# 16_FPGA_pwr_banks.net
KiCad netlist of a schematic drawn in Altium Designer
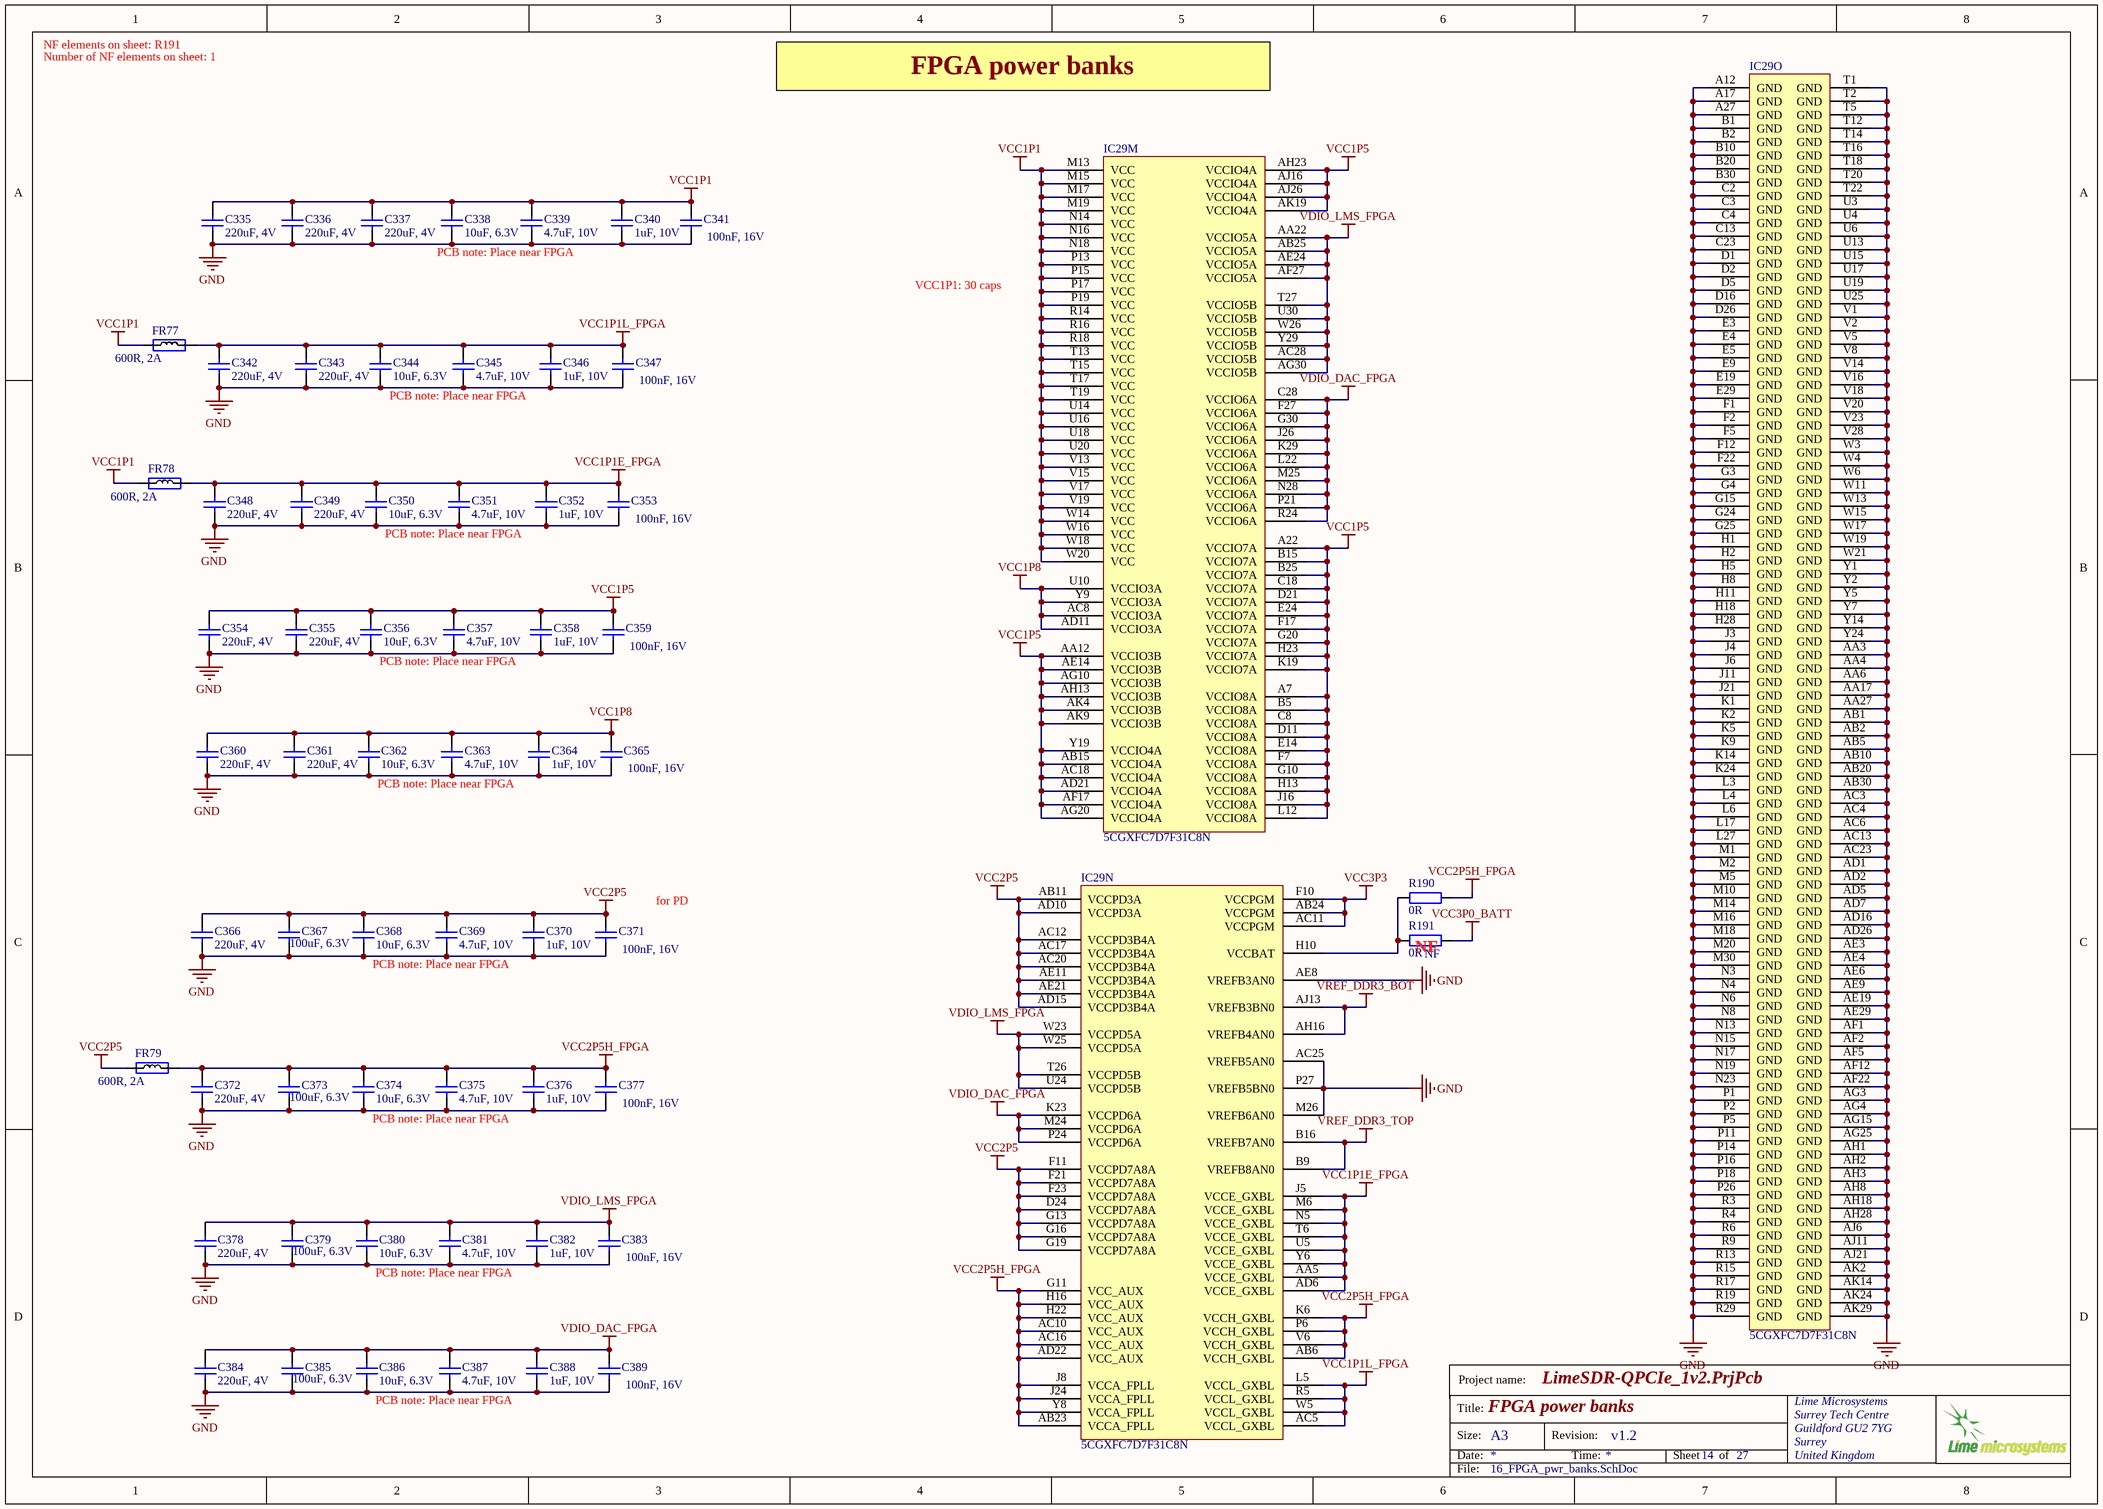
[diagram p0: 16_FPGA_pwr_banks.SchDoc]

(export (version "E")
  (design (tool "Eeschema 10.0.6"))
  (components
    (comp (ref "C335")
      (value "220uF, 4V")
      (footprint "CAP1206")
      (fields
        (field (name "MANUFACTURER PART NUMBER") "GRM31CR60G227ME11L")
        (field (name "MANUFACTURER") "Murata Electronics North America")
        (field (name "TOLERANCE") "±20%")
      )
      (libsource (lib "LimeFPGAboard_schLib") (part "Cap_1206"))
    )
    (comp (ref "C336")
      (value "220uF, 4V")
      (footprint "CAP1206")
      (fields
        (field (name "MANUFACTURER PART NUMBER") "GRM31CR60G227ME11L")
        (field (name "MANUFACTURER") "Murata Electronics North America")
        (field (name "TOLERANCE") "±20%")
      )
      (libsource (lib "LimeFPGAboard_schLib") (part "Cap_1206"))
    )
    (comp (ref "C337")
      (value "220uF, 4V")
      (footprint "CAP1206")
      (fields
        (field (name "MANUFACTURER PART NUMBER") "GRM31CR60G227ME11L")
        (field (name "MANUFACTURER") "Murata Electronics North America")
        (field (name "TOLERANCE") "±20%")
      )
      (libsource (lib "LimeFPGAboard_schLib") (part "Cap_1206"))
    )
    (comp (ref "C338")
      (value "10uF, 6.3V")
      (footprint "CAP0603")
      (fields (field (name "TOLERANCE") "±20%") (field (name "MANUFACTURER") "Yageo"))
      (libsource (lib "LimeFPGAboard_schLib") (part "Cap_0603"))
    )
    (comp (ref "C339")
      (value "4.7uF, 10V")
      (footprint "CAP0603")
      (fields (field (name "TOLERANCE") "10 %") (field (name "MANUFACTURER") "TDK Corporation"))
      (libsource (lib "LimeFPGAboard_schLib") (part "Cap_0603"))
    )
    (comp (ref "C340")
      (value "1uF, 10V")
      (footprint "CAP0402")
      (fields (field (name "MANUFACTURER") "TDK"))
      (libsource (lib "LimeMicroAltiumLib_schLib") (part "Cap_0402"))
    )
    (comp (ref "C341")
      (value "100nF, 16V")
      (footprint "CAP0402")
      (fields
        (field (name "TOLERANCE") "10 %")
        (field (name "MANUFACTURER") "Murata Electronics")
        (field (name "MANUFACTURER PART NUMBER") "GRM155R71C104KA88D")
      )
      (libsource (lib "LimeFPGAboard_schLib") (part "Cap_0603"))
    )
    (comp (ref "C342")
      (value "220uF, 4V")
      (footprint "CAP1206")
      (fields
        (field (name "MANUFACTURER PART NUMBER") "GRM31CR60G227ME11L")
        (field (name "MANUFACTURER") "Murata Electronics North America")
        (field (name "TOLERANCE") "±20%")
      )
      (libsource (lib "LimeFPGAboard_schLib") (part "Cap_1206"))
    )
    (comp (ref "C343")
      (value "220uF, 4V")
      (footprint "CAP1206")
      (fields
        (field (name "MANUFACTURER PART NUMBER") "GRM31CR60G227ME11L")
        (field (name "MANUFACTURER") "Murata Electronics North America")
        (field (name "TOLERANCE") "±20%")
      )
      (libsource (lib "LimeFPGAboard_schLib") (part "Cap_1206"))
    )
    (comp (ref "C344")
      (value "10uF, 6.3V")
      (footprint "CAP0603")
      (fields (field (name "TOLERANCE") "±20%") (field (name "MANUFACTURER") "Yageo"))
      (libsource (lib "LimeFPGAboard_schLib") (part "Cap_0603"))
    )
    (comp (ref "C345")
      (value "4.7uF, 10V")
      (footprint "CAP0603")
      (fields (field (name "TOLERANCE") "10 %") (field (name "MANUFACTURER") "TDK Corporation"))
      (libsource (lib "LimeFPGAboard_schLib") (part "Cap_0603"))
    )
    (comp (ref "C346")
      (value "1uF, 10V")
      (footprint "CAP0402")
      (fields (field (name "MANUFACTURER") "TDK"))
      (libsource (lib "LimeMicroAltiumLib_schLib") (part "Cap_0402"))
    )
    (comp (ref "C347")
      (value "100nF, 16V")
      (footprint "CAP0402")
      (fields
        (field (name "TOLERANCE") "10 %")
        (field (name "MANUFACTURER") "Murata Electronics")
        (field (name "MANUFACTURER PART NUMBER") "GRM155R71C104KA88D")
      )
      (libsource (lib "LimeFPGAboard_schLib") (part "Cap_0603"))
    )
    (comp (ref "C348")
      (value "220uF, 4V")
      (footprint "CAP1206")
      (fields
        (field (name "MANUFACTURER PART NUMBER") "GRM31CR60G227ME11L")
        (field (name "MANUFACTURER") "Murata Electronics North America")
        (field (name "TOLERANCE") "±20%")
      )
      (libsource (lib "LimeFPGAboard_schLib") (part "Cap_1206"))
    )
    (comp (ref "C349")
      (value "220uF, 4V")
      (footprint "CAP1206")
      (fields
        (field (name "MANUFACTURER PART NUMBER") "GRM31CR60G227ME11L")
        (field (name "MANUFACTURER") "Murata Electronics North America")
        (field (name "TOLERANCE") "±20%")
      )
      (libsource (lib "LimeFPGAboard_schLib") (part "Cap_1206"))
    )
    (comp (ref "C350")
      (value "10uF, 6.3V")
      (footprint "CAP0603")
      (fields (field (name "TOLERANCE") "±20%") (field (name "MANUFACTURER") "Yageo"))
      (libsource (lib "LimeFPGAboard_schLib") (part "Cap_0603"))
    )
    (comp (ref "C351")
      (value "4.7uF, 10V")
      (footprint "CAP0603")
      (fields (field (name "TOLERANCE") "10 %") (field (name "MANUFACTURER") "TDK Corporation"))
      (libsource (lib "LimeFPGAboard_schLib") (part "Cap_0603"))
    )
    (comp (ref "C352")
      (value "1uF, 10V")
      (footprint "CAP0402")
      (fields (field (name "MANUFACTURER") "TDK"))
      (libsource (lib "LimeMicroAltiumLib_schLib") (part "Cap_0402"))
    )
    (comp (ref "C353")
      (value "100nF, 16V")
      (footprint "CAP0402")
      (fields
        (field (name "TOLERANCE") "10 %")
        (field (name "MANUFACTURER") "Murata Electronics")
        (field (name "MANUFACTURER PART NUMBER") "GRM155R71C104KA88D")
      )
      (libsource (lib "LimeFPGAboard_schLib") (part "Cap_0603"))
    )
    (comp (ref "C354")
      (value "220uF, 4V")
      (footprint "CAP1206")
      (fields
        (field (name "MANUFACTURER PART NUMBER") "GRM31CR60G227ME11L")
        (field (name "MANUFACTURER") "Murata Electronics North America")
        (field (name "TOLERANCE") "±20%")
      )
      (libsource (lib "LimeFPGAboard_schLib") (part "Cap_1206"))
    )
    (comp (ref "C355")
      (value "220uF, 4V")
      (footprint "CAP1206")
      (fields
        (field (name "MANUFACTURER PART NUMBER") "GRM31CR60G227ME11L")
        (field (name "MANUFACTURER") "Murata Electronics North America")
        (field (name "TOLERANCE") "±20%")
      )
      (libsource (lib "LimeFPGAboard_schLib") (part "Cap_1206"))
    )
    (comp (ref "C356")
      (value "10uF, 6.3V")
      (footprint "CAP0603")
      (fields (field (name "TOLERANCE") "±20%") (field (name "MANUFACTURER") "Yageo"))
      (libsource (lib "LimeFPGAboard_schLib") (part "Cap_0603"))
    )
    (comp (ref "C357")
      (value "4.7uF, 10V")
      (footprint "CAP0603")
      (fields (field (name "TOLERANCE") "10 %") (field (name "MANUFACTURER") "TDK Corporation"))
      (libsource (lib "LimeFPGAboard_schLib") (part "Cap_0603"))
    )
    (comp (ref "C358")
      (value "1uF, 10V")
      (footprint "CAP0402")
      (fields (field (name "MANUFACTURER") "TDK"))
      (libsource (lib "LimeMicroAltiumLib_schLib") (part "Cap_0402"))
    )
    (comp (ref "C359")
      (value "100nF, 16V")
      (footprint "CAP0402")
      (fields
        (field (name "TOLERANCE") "10 %")
        (field (name "MANUFACTURER") "Murata Electronics")
        (field (name "MANUFACTURER PART NUMBER") "GRM155R71C104KA88D")
      )
      (libsource (lib "LimeFPGAboard_schLib") (part "Cap_0603"))
    )
    (comp (ref "C360")
      (value "220uF, 4V")
      (footprint "CAP1206")
      (fields
        (field (name "MANUFACTURER PART NUMBER") "GRM31CR60G227ME11L")
        (field (name "MANUFACTURER") "Murata Electronics North America")
        (field (name "TOLERANCE") "±20%")
      )
      (libsource (lib "LimeFPGAboard_schLib") (part "Cap_1206"))
    )
    (comp (ref "C361")
      (value "220uF, 4V")
      (footprint "CAP1206")
      (fields
        (field (name "MANUFACTURER PART NUMBER") "GRM31CR60G227ME11L")
        (field (name "MANUFACTURER") "Murata Electronics North America")
        (field (name "TOLERANCE") "±20%")
      )
      (libsource (lib "LimeFPGAboard_schLib") (part "Cap_1206"))
    )
    (comp (ref "C362")
      (value "10uF, 6.3V")
      (footprint "CAP0603")
      (fields (field (name "TOLERANCE") "±20%") (field (name "MANUFACTURER") "Yageo"))
      (libsource (lib "LimeFPGAboard_schLib") (part "Cap_0603"))
    )
    (comp (ref "C363")
      (value "4.7uF, 10V")
      (footprint "CAP0603")
      (fields (field (name "TOLERANCE") "10 %") (field (name "MANUFACTURER") "TDK Corporation"))
      (libsource (lib "LimeFPGAboard_schLib") (part "Cap_0603"))
    )
    (comp (ref "C364")
      (value "1uF, 10V")
      (footprint "CAP0402")
      (fields (field (name "MANUFACTURER") "TDK"))
      (libsource (lib "LimeMicroAltiumLib_schLib") (part "Cap_0402"))
    )
    (comp (ref "C365")
      (value "100nF, 16V")
      (footprint "CAP0402")
      (fields
        (field (name "TOLERANCE") "10 %")
        (field (name "MANUFACTURER") "Murata Electronics")
        (field (name "MANUFACTURER PART NUMBER") "GRM155R71C104KA88D")
      )
      (libsource (lib "LimeFPGAboard_schLib") (part "Cap_0603"))
    )
    (comp (ref "C366")
      (value "220uF, 4V")
      (footprint "CAP1206")
      (fields
        (field (name "MANUFACTURER PART NUMBER") "GRM31CR60G227ME11L")
        (field (name "MANUFACTURER") "Murata Electronics North America")
        (field (name "TOLERANCE") "±20%")
      )
      (libsource (lib "LimeFPGAboard_schLib") (part "Cap_1206"))
    )
    (comp (ref "C367")
      (value "100uF, 6.3V")
      (footprint "CAP1206")
      (fields (field (name "MANUFACTURER") "MURATA"))
      (libsource (lib "LimeFPGAboard_schLib") (part "Cap_1206"))
    )
    (comp (ref "C368")
      (value "10uF, 6.3V")
      (footprint "CAP0603")
      (fields (field (name "TOLERANCE") "±20%") (field (name "MANUFACTURER") "Yageo"))
      (libsource (lib "LimeFPGAboard_schLib") (part "Cap_0603"))
    )
    (comp (ref "C369")
      (value "4.7uF, 10V")
      (footprint "CAP0603")
      (fields (field (name "TOLERANCE") "10 %") (field (name "MANUFACTURER") "TDK Corporation"))
      (libsource (lib "LimeFPGAboard_schLib") (part "Cap_0603"))
    )
    (comp (ref "C370")
      (value "1uF, 10V")
      (footprint "CAP0402")
      (fields (field (name "MANUFACTURER") "TDK"))
      (libsource (lib "LimeMicroAltiumLib_schLib") (part "Cap_0402"))
    )
    (comp (ref "C371")
      (value "100nF, 16V")
      (footprint "CAP0402")
      (fields
        (field (name "TOLERANCE") "10 %")
        (field (name "MANUFACTURER") "Murata Electronics")
        (field (name "MANUFACTURER PART NUMBER") "GRM155R71C104KA88D")
      )
      (libsource (lib "LimeFPGAboard_schLib") (part "Cap_0603"))
    )
    (comp (ref "C372")
      (value "220uF, 4V")
      (footprint "CAP1206")
      (fields
        (field (name "MANUFACTURER PART NUMBER") "GRM31CR60G227ME11L")
        (field (name "MANUFACTURER") "Murata Electronics North America")
        (field (name "TOLERANCE") "±20%")
      )
      (libsource (lib "LimeFPGAboard_schLib") (part "Cap_1206"))
    )
    (comp (ref "C373")
      (value "100uF, 6.3V")
      (footprint "CAP1206")
      (fields (field (name "MANUFACTURER") "MURATA"))
      (libsource (lib "LimeFPGAboard_schLib") (part "Cap_1206"))
    )
    (comp (ref "C374")
      (value "10uF, 6.3V")
      (footprint "CAP0603")
      (fields (field (name "TOLERANCE") "±20%") (field (name "MANUFACTURER") "Yageo"))
      (libsource (lib "LimeFPGAboard_schLib") (part "Cap_0603"))
    )
    (comp (ref "C375")
      (value "4.7uF, 10V")
      (footprint "CAP0603")
      (fields (field (name "TOLERANCE") "10 %") (field (name "MANUFACTURER") "TDK Corporation"))
      (libsource (lib "LimeFPGAboard_schLib") (part "Cap_0603"))
    )
    (comp (ref "C376")
      (value "1uF, 10V")
      (footprint "CAP0402")
      (fields (field (name "MANUFACTURER") "TDK"))
      (libsource (lib "LimeMicroAltiumLib_schLib") (part "Cap_0402"))
    )
    (comp (ref "C377")
      (value "100nF, 16V")
      (footprint "CAP0402")
      (fields
        (field (name "TOLERANCE") "10 %")
        (field (name "MANUFACTURER") "Murata Electronics")
        (field (name "MANUFACTURER PART NUMBER") "GRM155R71C104KA88D")
      )
      (libsource (lib "LimeFPGAboard_schLib") (part "Cap_0603"))
    )
    (comp (ref "C378")
      (value "220uF, 4V")
      (footprint "CAP1206")
      (fields
        (field (name "MANUFACTURER PART NUMBER") "GRM31CR60G227ME11L")
        (field (name "MANUFACTURER") "Murata Electronics North America")
        (field (name "TOLERANCE") "±20%")
      )
      (libsource (lib "LimeFPGAboard_schLib") (part "Cap_1206"))
    )
    (comp (ref "C379")
      (value "100uF, 6.3V")
      (footprint "CAP1206")
      (fields (field (name "MANUFACTURER") "MURATA"))
      (libsource (lib "LimeFPGAboard_schLib") (part "Cap_1206"))
    )
    (comp (ref "C380")
      (value "10uF, 6.3V")
      (footprint "CAP0603")
      (fields (field (name "TOLERANCE") "±20%") (field (name "MANUFACTURER") "Yageo"))
      (libsource (lib "LimeFPGAboard_schLib") (part "Cap_0603"))
    )
    (comp (ref "C381")
      (value "4.7uF, 10V")
      (footprint "CAP0603")
      (fields (field (name "TOLERANCE") "10 %") (field (name "MANUFACTURER") "TDK Corporation"))
      (libsource (lib "LimeFPGAboard_schLib") (part "Cap_0603"))
    )
    (comp (ref "C382")
      (value "1uF, 10V")
      (footprint "CAP0402")
      (fields (field (name "MANUFACTURER") "TDK"))
      (libsource (lib "LimeMicroAltiumLib_schLib") (part "Cap_0402"))
    )
    (comp (ref "C383")
      (value "100nF, 16V")
      (footprint "CAP0402")
      (fields
        (field (name "TOLERANCE") "10 %")
        (field (name "MANUFACTURER") "Murata Electronics")
        (field (name "MANUFACTURER PART NUMBER") "GRM155R71C104KA88D")
      )
      (libsource (lib "LimeFPGAboard_schLib") (part "Cap_0603"))
    )
    (comp (ref "C384")
      (value "220uF, 4V")
      (footprint "CAP1206")
      (fields
        (field (name "MANUFACTURER PART NUMBER") "GRM31CR60G227ME11L")
        (field (name "MANUFACTURER") "Murata Electronics North America")
        (field (name "TOLERANCE") "±20%")
      )
      (libsource (lib "LimeFPGAboard_schLib") (part "Cap_1206"))
    )
    (comp (ref "C385")
      (value "100uF, 6.3V")
      (footprint "CAP1206")
      (fields (field (name "MANUFACTURER") "MURATA"))
      (libsource (lib "LimeFPGAboard_schLib") (part "Cap_1206"))
    )
    (comp (ref "C386")
      (value "10uF, 6.3V")
      (footprint "CAP0603")
      (fields (field (name "TOLERANCE") "±20%") (field (name "MANUFACTURER") "Yageo"))
      (libsource (lib "LimeFPGAboard_schLib") (part "Cap_0603"))
    )
    (comp (ref "C387")
      (value "4.7uF, 10V")
      (footprint "CAP0603")
      (fields (field (name "TOLERANCE") "10 %") (field (name "MANUFACTURER") "TDK Corporation"))
      (libsource (lib "LimeFPGAboard_schLib") (part "Cap_0603"))
    )
    (comp (ref "C388")
      (value "1uF, 10V")
      (footprint "CAP0402")
      (fields (field (name "MANUFACTURER") "TDK"))
      (libsource (lib "LimeMicroAltiumLib_schLib") (part "Cap_0402"))
    )
    (comp (ref "C389")
      (value "100nF, 16V")
      (footprint "CAP0402")
      (fields
        (field (name "TOLERANCE") "10 %")
        (field (name "MANUFACTURER") "Murata Electronics")
        (field (name "MANUFACTURER PART NUMBER") "GRM155R71C104KA88D")
      )
      (libsource (lib "LimeFPGAboard_schLib") (part "Cap_0603"))
    )
    (comp (ref "FR77")
      (value "600R, 2A")
      (footprint "RES0805")
      (fields (field (name "MANUFACTURER") "TDK"))
      (libsource (lib "LimeMicroAltiumLib_schLib") (part "Ferrite"))
    )
    (comp (ref "FR78")
      (value "600R, 2A")
      (footprint "RES0805")
      (fields (field (name "MANUFACTURER") "TDK"))
      (libsource (lib "LimeMicroAltiumLib_schLib") (part "Ferrite"))
    )
    (comp (ref "FR79")
      (value "600R, 2A")
      (footprint "RES0805")
      (fields (field (name "MANUFACTURER") "TDK"))
      (libsource (lib "LimeMicroAltiumLib_schLib") (part "Ferrite"))
    )
    (comp (ref "IC29")
      (value "5CGXFC7D7F31C8N")
      (footprint "ALTR-FBGA896_A-200")
      (fields (field (name "MANUFACTURER") "Altera"))
      (libsource (lib "LimeMicroAltiumLib_schLib") (part "5CGXFC7D7F31C8N"))
    )
    (comp (ref "R190")
      (value "0R")
      (footprint "RES0402")
      (fields (field (name "MANUFACTURER") "Yageo") (field (name "TOLERANCE") "Jumper"))
      (libsource (lib "LimeMicroAltiumLib_schLib") (part "Res_0402"))
    )
    (comp (ref "R191")
      (value "0R")
      (footprint "RES0402")
      (fields
        (field (name "ASSEMBLY INFO") "NF")
        (field (name "MANUFACTURER") "Yageo")
        (field (name "TOLERANCE") "Jumper")
      )
      (libsource (lib "LimeMicroAltiumLib_schLib") (part "Res_0402"))
    )
  )
  (nets
    (net (code "1") (name "GND") (class "Default")
      (node (ref "C335") (pin "1") (pinfunction "1_1") (pintype "passive"))
      (node (ref "C336") (pin "1") (pinfunction "1_1") (pintype "passive"))
      (node (ref "C337") (pin "1") (pinfunction "1_1") (pintype "passive"))
      (node (ref "C338") (pin "1") (pinfunction "1_1") (pintype "passive"))
      (node (ref "C339") (pin "1") (pinfunction "1_1") (pintype "passive"))
      (node (ref "C340") (pin "2") (pinfunction "2_2") (pintype "passive"))
      (node (ref "C341") (pin "2") (pinfunction "2_2") (pintype "passive"))
      (node (ref "C342") (pin "1") (pinfunction "1_1") (pintype "passive"))
      (node (ref "C343") (pin "1") (pinfunction "1_1") (pintype "passive"))
      (node (ref "C344") (pin "1") (pinfunction "1_1") (pintype "passive"))
      (node (ref "C345") (pin "1") (pinfunction "1_1") (pintype "passive"))
      (node (ref "C346") (pin "1") (pinfunction "1_1") (pintype "passive"))
      (node (ref "C347") (pin "2") (pinfunction "2_2") (pintype "passive"))
      (node (ref "C348") (pin "1") (pinfunction "1_1") (pintype "passive"))
      (node (ref "C349") (pin "1") (pinfunction "1_1") (pintype "passive"))
      (node (ref "C350") (pin "1") (pinfunction "1_1") (pintype "passive"))
      (node (ref "C351") (pin "1") (pinfunction "1_1") (pintype "passive"))
      (node (ref "C352") (pin "1") (pinfunction "1_1") (pintype "passive"))
      (node (ref "C353") (pin "2") (pinfunction "2_2") (pintype "passive"))
      (node (ref "C354") (pin "1") (pinfunction "1_1") (pintype "passive"))
      (node (ref "C355") (pin "1") (pinfunction "1_1") (pintype "passive"))
      (node (ref "C356") (pin "1") (pinfunction "1_1") (pintype "passive"))
      (node (ref "C357") (pin "1") (pinfunction "1_1") (pintype "passive"))
      (node (ref "C358") (pin "1") (pinfunction "1_1") (pintype "passive"))
      (node (ref "C359") (pin "2") (pinfunction "2_2") (pintype "passive"))
      (node (ref "C360") (pin "1") (pinfunction "1_1") (pintype "passive"))
      (node (ref "C361") (pin "1") (pinfunction "1_1") (pintype "passive"))
      (node (ref "C362") (pin "1") (pinfunction "1_1") (pintype "passive"))
      (node (ref "C363") (pin "1") (pinfunction "1_1") (pintype "passive"))
      (node (ref "C364") (pin "1") (pinfunction "1_1") (pintype "passive"))
      (node (ref "C365") (pin "2") (pinfunction "2_2") (pintype "passive"))
      (node (ref "C366") (pin "1") (pinfunction "1_1") (pintype "passive"))
      (node (ref "C367") (pin "1") (pinfunction "1_1") (pintype "passive"))
      (node (ref "C368") (pin "1") (pinfunction "1_1") (pintype "passive"))
      (node (ref "C369") (pin "1") (pinfunction "1_1") (pintype "passive"))
      (node (ref "C370") (pin "1") (pinfunction "1_1") (pintype "passive"))
      (node (ref "C371") (pin "2") (pinfunction "2_2") (pintype "passive"))
      (node (ref "C372") (pin "1") (pinfunction "1_1") (pintype "passive"))
      (node (ref "C373") (pin "1") (pinfunction "1_1") (pintype "passive"))
      (node (ref "C374") (pin "1") (pinfunction "1_1") (pintype "passive"))
      (node (ref "C375") (pin "1") (pinfunction "1_1") (pintype "passive"))
      (node (ref "C376") (pin "1") (pinfunction "1_1") (pintype "passive"))
      (node (ref "C377") (pin "2") (pinfunction "2_2") (pintype "passive"))
      (node (ref "C378") (pin "1") (pinfunction "1_1") (pintype "passive"))
      (node (ref "C379") (pin "1") (pinfunction "1_1") (pintype "passive"))
      (node (ref "C380") (pin "1") (pinfunction "1_1") (pintype "passive"))
      (node (ref "C381") (pin "1") (pinfunction "1_1") (pintype "passive"))
      (node (ref "C382") (pin "1") (pinfunction "1_1") (pintype "passive"))
      (node (ref "C383") (pin "2") (pinfunction "2_2") (pintype "passive"))
      (node (ref "C384") (pin "1") (pinfunction "1_1") (pintype "passive"))
      (node (ref "C385") (pin "1") (pinfunction "1_1") (pintype "passive"))
      (node (ref "C386") (pin "1") (pinfunction "1_1") (pintype "passive"))
      (node (ref "C387") (pin "1") (pinfunction "1_1") (pintype "passive"))
      (node (ref "C388") (pin "1") (pinfunction "1_1") (pintype "passive"))
      (node (ref "C389") (pin "2") (pinfunction "2_2") (pintype "passive"))
      (node (ref "IC29") (pin "A12") (pinfunction "GND_A12") (pintype "power_in"))
      (node (ref "IC29") (pin "A17") (pinfunction "GND_A17") (pintype "power_in"))
      (node (ref "IC29") (pin "A27") (pinfunction "GND_A27") (pintype "power_in"))
      (node (ref "IC29") (pin "AA17") (pinfunction "GND_AA17") (pintype "power_in"))
      (node (ref "IC29") (pin "AA27") (pinfunction "GND_AA27") (pintype "power_in"))
      (node (ref "IC29") (pin "AA3") (pinfunction "GND_AA3") (pintype "power_in"))
      (node (ref "IC29") (pin "AA4") (pinfunction "GND_AA4") (pintype "power_in"))
      (node (ref "IC29") (pin "AA6") (pinfunction "GND_AA6") (pintype "power_in"))
      (node (ref "IC29") (pin "AB1") (pinfunction "GND_AB1") (pintype "power_in"))
      (node (ref "IC29") (pin "AB10") (pinfunction "GND_AB10") (pintype "power_in"))
      (node (ref "IC29") (pin "AB2") (pinfunction "GND_AB2") (pintype "power_in"))
      (node (ref "IC29") (pin "AB20") (pinfunction "GND_AB20") (pintype "power_in"))
      (node (ref "IC29") (pin "AB30") (pinfunction "GND_AB30") (pintype "power_in"))
      (node (ref "IC29") (pin "AB5") (pinfunction "GND_AB5") (pintype "power_in"))
      (node (ref "IC29") (pin "AC13") (pinfunction "GND_AC13") (pintype "power_in"))
      (node (ref "IC29") (pin "AC23") (pinfunction "GND_AC23") (pintype "power_in"))
      (node (ref "IC29") (pin "AC25") (pinfunction "VREFB5AN0_AC25") (pintype "power_in"))
      (node (ref "IC29") (pin "AC3") (pinfunction "GND_AC3") (pintype "power_in"))
      (node (ref "IC29") (pin "AC4") (pinfunction "GND_AC4") (pintype "power_in"))
      (node (ref "IC29") (pin "AC6") (pinfunction "GND_AC6") (pintype "power_in"))
      (node (ref "IC29") (pin "AD1") (pinfunction "GND_AD1") (pintype "power_in"))
      (node (ref "IC29") (pin "AD16") (pinfunction "GND_AD16") (pintype "power_in"))
      (node (ref "IC29") (pin "AD2") (pinfunction "GND_AD2") (pintype "power_in"))
      (node (ref "IC29") (pin "AD26") (pinfunction "GND_AD26") (pintype "power_in"))
      (node (ref "IC29") (pin "AD5") (pinfunction "GND_AD5") (pintype "power_in"))
      (node (ref "IC29") (pin "AD7") (pinfunction "GND_AD7") (pintype "power_in"))
      (node (ref "IC29") (pin "AE19") (pinfunction "GND_AE19") (pintype "power_in"))
      (node (ref "IC29") (pin "AE29") (pinfunction "GND_AE29") (pintype "power_in"))
      (node (ref "IC29") (pin "AE3") (pinfunction "GND_AE3") (pintype "power_in"))
      (node (ref "IC29") (pin "AE4") (pinfunction "GND_AE4") (pintype "power_in"))
      (node (ref "IC29") (pin "AE6") (pinfunction "GND_AE6") (pintype "power_in"))
      (node (ref "IC29") (pin "AE8") (pinfunction "VREFB3AN0_AE8") (pintype "power_in"))
      (node (ref "IC29") (pin "AE9") (pinfunction "GND_AE9") (pintype "power_in"))
      (node (ref "IC29") (pin "AF1") (pinfunction "GND_AF1") (pintype "power_in"))
      (node (ref "IC29") (pin "AF12") (pinfunction "GND_AF12") (pintype "power_in"))
      (node (ref "IC29") (pin "AF2") (pinfunction "GND_AF2") (pintype "power_in"))
      (node (ref "IC29") (pin "AF22") (pinfunction "GND_AF22") (pintype "power_in"))
      (node (ref "IC29") (pin "AF5") (pinfunction "GND_AF5") (pintype "power_in"))
      (node (ref "IC29") (pin "AG15") (pinfunction "GND_AG15") (pintype "power_in"))
      (node (ref "IC29") (pin "AG25") (pinfunction "GND_AG25") (pintype "power_in"))
      (node (ref "IC29") (pin "AG3") (pinfunction "GND_AG3") (pintype "power_in"))
      (node (ref "IC29") (pin "AG4") (pinfunction "GND_AG4") (pintype "power_in"))
      (node (ref "IC29") (pin "AH1") (pinfunction "GND_AH1") (pintype "power_in"))
      (node (ref "IC29") (pin "AH18") (pinfunction "GND_AH18") (pintype "power_in"))
      (node (ref "IC29") (pin "AH2") (pinfunction "GND_AH2") (pintype "power_in"))
      (node (ref "IC29") (pin "AH28") (pinfunction "GND_AH28") (pintype "power_in"))
      (node (ref "IC29") (pin "AH3") (pinfunction "GND_AH3") (pintype "power_in"))
      (node (ref "IC29") (pin "AH8") (pinfunction "GND_AH8") (pintype "power_in"))
      (node (ref "IC29") (pin "AJ11") (pinfunction "GND_AJ11") (pintype "power_in"))
      (node (ref "IC29") (pin "AJ21") (pinfunction "GND_AJ21") (pintype "power_in"))
      (node (ref "IC29") (pin "AJ6") (pinfunction "GND_AJ6") (pintype "power_in"))
      (node (ref "IC29") (pin "AK14") (pinfunction "GND_AK14") (pintype "power_in"))
      (node (ref "IC29") (pin "AK2") (pinfunction "GND_AK2") (pintype "power_in"))
      (node (ref "IC29") (pin "AK24") (pinfunction "GND_AK24") (pintype "power_in"))
      (node (ref "IC29") (pin "AK29") (pinfunction "GND_AK29") (pintype "power_in"))
      (node (ref "IC29") (pin "B1") (pinfunction "GND_B1") (pintype "power_in"))
      (node (ref "IC29") (pin "B10") (pinfunction "GND_B10") (pintype "power_in"))
      (node (ref "IC29") (pin "B2") (pinfunction "GND_B2") (pintype "power_in"))
      (node (ref "IC29") (pin "B20") (pinfunction "GND_B20") (pintype "power_in"))
      (node (ref "IC29") (pin "B30") (pinfunction "GND_B30") (pintype "power_in"))
      (node (ref "IC29") (pin "C13") (pinfunction "GND_C13") (pintype "power_in"))
      (node (ref "IC29") (pin "C2") (pinfunction "GND_C2") (pintype "power_in"))
      (node (ref "IC29") (pin "C23") (pinfunction "GND_C23") (pintype "power_in"))
      (node (ref "IC29") (pin "C3") (pinfunction "GND_C3") (pintype "power_in"))
      (node (ref "IC29") (pin "C4") (pinfunction "GND_C4") (pintype "power_in"))
      (node (ref "IC29") (pin "D1") (pinfunction "GND_D1") (pintype "power_in"))
      (node (ref "IC29") (pin "D16") (pinfunction "GND_D16") (pintype "power_in"))
      (node (ref "IC29") (pin "D2") (pinfunction "GND_D2") (pintype "power_in"))
      (node (ref "IC29") (pin "D26") (pinfunction "GND_D26") (pintype "power_in"))
      (node (ref "IC29") (pin "D5") (pinfunction "GND_D5") (pintype "power_in"))
      (node (ref "IC29") (pin "E19") (pinfunction "GND_E19") (pintype "power_in"))
      (node (ref "IC29") (pin "E29") (pinfunction "GND_E29") (pintype "power_in"))
      (node (ref "IC29") (pin "E3") (pinfunction "GND_E3") (pintype "power_in"))
      (node (ref "IC29") (pin "E4") (pinfunction "GND_E4") (pintype "power_in"))
      (node (ref "IC29") (pin "E5") (pinfunction "GND_E5") (pintype "power_in"))
      (node (ref "IC29") (pin "E9") (pinfunction "GND_E9") (pintype "power_in"))
      (node (ref "IC29") (pin "F1") (pinfunction "GND_F1") (pintype "power_in"))
      (node (ref "IC29") (pin "F12") (pinfunction "GND_F12") (pintype "power_in"))
      (node (ref "IC29") (pin "F2") (pinfunction "GND_F2") (pintype "power_in"))
      (node (ref "IC29") (pin "F22") (pinfunction "GND_F22") (pintype "power_in"))
      (node (ref "IC29") (pin "F5") (pinfunction "GND_F5") (pintype "power_in"))
      (node (ref "IC29") (pin "G15") (pinfunction "GND_G15") (pintype "power_in"))
      (node (ref "IC29") (pin "G24") (pinfunction "GND_G24") (pintype "power_in"))
      (node (ref "IC29") (pin "G25") (pinfunction "GND_G25") (pintype "power_in"))
      (node (ref "IC29") (pin "G3") (pinfunction "GND_G3") (pintype "power_in"))
      (node (ref "IC29") (pin "G4") (pinfunction "GND_G4") (pintype "power_in"))
      (node (ref "IC29") (pin "H1") (pinfunction "GND_H1") (pintype "power_in"))
      (node (ref "IC29") (pin "H11") (pinfunction "GND_H11") (pintype "power_in"))
      (node (ref "IC29") (pin "H18") (pinfunction "GND_H18") (pintype "power_in"))
      (node (ref "IC29") (pin "H2") (pinfunction "GND_H2") (pintype "power_in"))
      (node (ref "IC29") (pin "H28") (pinfunction "GND_H28") (pintype "power_in"))
      (node (ref "IC29") (pin "H5") (pinfunction "GND_H5") (pintype "power_in"))
      (node (ref "IC29") (pin "H8") (pinfunction "GND_H8") (pintype "power_in"))
      (node (ref "IC29") (pin "J11") (pinfunction "GND_J11") (pintype "power_in"))
      (node (ref "IC29") (pin "J21") (pinfunction "GND_J21") (pintype "power_in"))
      (node (ref "IC29") (pin "J3") (pinfunction "GND_J3") (pintype "power_in"))
      (node (ref "IC29") (pin "J4") (pinfunction "GND_J4") (pintype "power_in"))
      (node (ref "IC29") (pin "J6") (pinfunction "GND_J6") (pintype "power_in"))
      (node (ref "IC29") (pin "K1") (pinfunction "GND_K1") (pintype "power_in"))
      (node (ref "IC29") (pin "K14") (pinfunction "GND_K14") (pintype "power_in"))
      (node (ref "IC29") (pin "K2") (pinfunction "GND_K2") (pintype "power_in"))
      (node (ref "IC29") (pin "K24") (pinfunction "GND_K24") (pintype "power_in"))
      (node (ref "IC29") (pin "K5") (pinfunction "GND_K5") (pintype "power_in"))
      (node (ref "IC29") (pin "K9") (pinfunction "GND_K9") (pintype "power_in"))
      (node (ref "IC29") (pin "L17") (pinfunction "GND_L17") (pintype "power_in"))
      (node (ref "IC29") (pin "L27") (pinfunction "GND_L27") (pintype "power_in"))
      (node (ref "IC29") (pin "L3") (pinfunction "GND_L3") (pintype "power_in"))
      (node (ref "IC29") (pin "L4") (pinfunction "GND_L4") (pintype "power_in"))
      (node (ref "IC29") (pin "L6") (pinfunction "GND_L6") (pintype "power_in"))
      (node (ref "IC29") (pin "M1") (pinfunction "GND_M1") (pintype "power_in"))
      (node (ref "IC29") (pin "M10") (pinfunction "GND_M10") (pintype "power_in"))
      (node (ref "IC29") (pin "M14") (pinfunction "GND_M14") (pintype "power_in"))
      (node (ref "IC29") (pin "M16") (pinfunction "GND_M16") (pintype "power_in"))
      (node (ref "IC29") (pin "M18") (pinfunction "GND_M18") (pintype "power_in"))
      (node (ref "IC29") (pin "M2") (pinfunction "GND_M2") (pintype "power_in"))
      (node (ref "IC29") (pin "M20") (pinfunction "GND_M20") (pintype "power_in"))
      (node (ref "IC29") (pin "M26") (pinfunction "VREFB6AN0_M26") (pintype "power_in"))
      (node (ref "IC29") (pin "M30") (pinfunction "GND_M30") (pintype "power_in"))
      (node (ref "IC29") (pin "M5") (pinfunction "GND_M5") (pintype "power_in"))
      (node (ref "IC29") (pin "N13") (pinfunction "GND_N13") (pintype "power_in"))
      (node (ref "IC29") (pin "N15") (pinfunction "GND_N15") (pintype "power_in"))
      (node (ref "IC29") (pin "N17") (pinfunction "GND_N17") (pintype "power_in"))
      (node (ref "IC29") (pin "N19") (pinfunction "GND_N19") (pintype "power_in"))
      (node (ref "IC29") (pin "N23") (pinfunction "GND_N23") (pintype "power_in"))
      (node (ref "IC29") (pin "N3") (pinfunction "GND_N3") (pintype "power_in"))
      (node (ref "IC29") (pin "N4") (pinfunction "GND_N4") (pintype "power_in"))
      (node (ref "IC29") (pin "N6") (pinfunction "GND_N6") (pintype "power_in"))
      (node (ref "IC29") (pin "N8") (pinfunction "GND_N8") (pintype "power_in"))
      (node (ref "IC29") (pin "P1") (pinfunction "GND_P1") (pintype "power_in"))
      (node (ref "IC29") (pin "P11") (pinfunction "GND_P11") (pintype "power_in"))
      (node (ref "IC29") (pin "P14") (pinfunction "GND_P14") (pintype "power_in"))
      (node (ref "IC29") (pin "P16") (pinfunction "GND_P16") (pintype "power_in"))
      (node (ref "IC29") (pin "P18") (pinfunction "GND_P18") (pintype "power_in"))
      (node (ref "IC29") (pin "P2") (pinfunction "GND_P2") (pintype "power_in"))
      (node (ref "IC29") (pin "P26") (pinfunction "GND_P26") (pintype "power_in"))
      (node (ref "IC29") (pin "P27") (pinfunction "VREFB5BN0_P27") (pintype "power_in"))
      (node (ref "IC29") (pin "P5") (pinfunction "GND_P5") (pintype "power_in"))
      (node (ref "IC29") (pin "R13") (pinfunction "GND_R13") (pintype "power_in"))
      (node (ref "IC29") (pin "R15") (pinfunction "GND_R15") (pintype "power_in"))
      (node (ref "IC29") (pin "R17") (pinfunction "GND_R17") (pintype "power_in"))
      (node (ref "IC29") (pin "R19") (pinfunction "GND_R19") (pintype "power_in"))
      (node (ref "IC29") (pin "R29") (pinfunction "GND_R29") (pintype "power_in"))
      (node (ref "IC29") (pin "R3") (pinfunction "GND_R3") (pintype "power_in"))
      (node (ref "IC29") (pin "R4") (pinfunction "GND_R4") (pintype "power_in"))
      (node (ref "IC29") (pin "R6") (pinfunction "GND_R6") (pintype "power_in"))
      (node (ref "IC29") (pin "R9") (pinfunction "GND_R9") (pintype "power_in"))
      (node (ref "IC29") (pin "T1") (pinfunction "GND_T1") (pintype "power_in"))
      (node (ref "IC29") (pin "T12") (pinfunction "GND_T12") (pintype "power_in"))
      (node (ref "IC29") (pin "T14") (pinfunction "GND_T14") (pintype "power_in"))
      (node (ref "IC29") (pin "T16") (pinfunction "GND_T16") (pintype "power_in"))
      (node (ref "IC29") (pin "T18") (pinfunction "GND_T18") (pintype "power_in"))
      (node (ref "IC29") (pin "T2") (pinfunction "GND_T2") (pintype "power_in"))
      (node (ref "IC29") (pin "T20") (pinfunction "GND_T20") (pintype "power_in"))
      (node (ref "IC29") (pin "T22") (pinfunction "GND_T22") (pintype "power_in"))
      (node (ref "IC29") (pin "T5") (pinfunction "GND_T5") (pintype "power_in"))
      (node (ref "IC29") (pin "U13") (pinfunction "GND_U13") (pintype "power_in"))
      (node (ref "IC29") (pin "U15") (pinfunction "GND_U15") (pintype "power_in"))
      (node (ref "IC29") (pin "U17") (pinfunction "GND_U17") (pintype "power_in"))
      (node (ref "IC29") (pin "U19") (pinfunction "GND_U19") (pintype "power_in"))
      (node (ref "IC29") (pin "U25") (pinfunction "GND_U25") (pintype "power_in"))
      (node (ref "IC29") (pin "U3") (pinfunction "GND_U3") (pintype "power_in"))
      (node (ref "IC29") (pin "U4") (pinfunction "GND_U4") (pintype "power_in"))
      (node (ref "IC29") (pin "U6") (pinfunction "GND_U6") (pintype "power_in"))
      (node (ref "IC29") (pin "V1") (pinfunction "GND_V1") (pintype "power_in"))
      (node (ref "IC29") (pin "V14") (pinfunction "GND_V14") (pintype "power_in"))
      (node (ref "IC29") (pin "V16") (pinfunction "GND_V16") (pintype "power_in"))
      (node (ref "IC29") (pin "V18") (pinfunction "GND_V18") (pintype "power_in"))
      (node (ref "IC29") (pin "V2") (pinfunction "GND_V2") (pintype "power_in"))
      (node (ref "IC29") (pin "V20") (pinfunction "GND_V20") (pintype "power_in"))
      (node (ref "IC29") (pin "V23") (pinfunction "GND_V23") (pintype "power_in"))
      (node (ref "IC29") (pin "V28") (pinfunction "GND_V28") (pintype "power_in"))
      (node (ref "IC29") (pin "V5") (pinfunction "GND_V5") (pintype "power_in"))
      (node (ref "IC29") (pin "V8") (pinfunction "GND_V8") (pintype "power_in"))
      (node (ref "IC29") (pin "W11") (pinfunction "GND_W11") (pintype "power_in"))
      (node (ref "IC29") (pin "W13") (pinfunction "GND_W13") (pintype "power_in"))
      (node (ref "IC29") (pin "W15") (pinfunction "GND_W15") (pintype "power_in"))
      (node (ref "IC29") (pin "W17") (pinfunction "GND_W17") (pintype "power_in"))
      (node (ref "IC29") (pin "W19") (pinfunction "GND_W19") (pintype "power_in"))
      (node (ref "IC29") (pin "W21") (pinfunction "GND_W21") (pintype "power_in"))
      (node (ref "IC29") (pin "W3") (pinfunction "GND_W3") (pintype "power_in"))
      (node (ref "IC29") (pin "W4") (pinfunction "GND_W4") (pintype "power_in"))
      (node (ref "IC29") (pin "W6") (pinfunction "GND_W6") (pintype "power_in"))
      (node (ref "IC29") (pin "Y1") (pinfunction "GND_Y1") (pintype "power_in"))
      (node (ref "IC29") (pin "Y14") (pinfunction "GND_Y14") (pintype "power_in"))
      (node (ref "IC29") (pin "Y2") (pinfunction "GND_Y2") (pintype "power_in"))
      (node (ref "IC29") (pin "Y24") (pinfunction "GND_Y24") (pintype "power_in"))
      (node (ref "IC29") (pin "Y5") (pinfunction "GND_Y5") (pintype "power_in"))
      (node (ref "IC29") (pin "Y7") (pinfunction "GND_Y7") (pintype "power_in"))
    )
    (net (code "2") (name "Net-(IC29N-VCCBAT)") (class "Default")
      (node (ref "IC29") (pin "H10") (pinfunction "VCCBAT_H10") (pintype "power_in"))
      (node (ref "R190") (pin "2") (pinfunction "2_2") (pintype "passive"))
      (node (ref "R191") (pin "2") (pinfunction "2_2") (pintype "passive"))
    )
    (net (code "3") (name "VCC1P1") (class "Default")
      (node (ref "C335") (pin "2") (pinfunction "2_2") (pintype "passive"))
      (node (ref "C336") (pin "2") (pinfunction "2_2") (pintype "passive"))
      (node (ref "C337") (pin "2") (pinfunction "2_2") (pintype "passive"))
      (node (ref "C338") (pin "2") (pinfunction "2_2") (pintype "passive"))
      (node (ref "C339") (pin "2") (pinfunction "2_2") (pintype "passive"))
      (node (ref "C340") (pin "1") (pinfunction "1_1") (pintype "passive"))
      (node (ref "C341") (pin "1") (pinfunction "1_1") (pintype "passive"))
      (node (ref "FR77") (pin "1") (pinfunction "1_1") (pintype "passive"))
      (node (ref "FR78") (pin "1") (pinfunction "1_1") (pintype "passive"))
      (node (ref "IC29") (pin "M13") (pinfunction "VCC_M13") (pintype "power_in"))
      (node (ref "IC29") (pin "M15") (pinfunction "VCC_M15") (pintype "power_in"))
      (node (ref "IC29") (pin "M17") (pinfunction "VCC_M17") (pintype "power_in"))
      (node (ref "IC29") (pin "M19") (pinfunction "VCC_M19") (pintype "power_in"))
      (node (ref "IC29") (pin "N14") (pinfunction "VCC_N14") (pintype "power_in"))
      (node (ref "IC29") (pin "N16") (pinfunction "VCC_N16") (pintype "power_in"))
      (node (ref "IC29") (pin "N18") (pinfunction "VCC_N18") (pintype "power_in"))
      (node (ref "IC29") (pin "P13") (pinfunction "VCC_P13") (pintype "power_in"))
      (node (ref "IC29") (pin "P15") (pinfunction "VCC_P15") (pintype "power_in"))
      (node (ref "IC29") (pin "P17") (pinfunction "VCC_P17") (pintype "power_in"))
      (node (ref "IC29") (pin "P19") (pinfunction "VCC_P19") (pintype "power_in"))
      (node (ref "IC29") (pin "R14") (pinfunction "VCC_R14") (pintype "power_in"))
      (node (ref "IC29") (pin "R16") (pinfunction "VCC_R16") (pintype "power_in"))
      (node (ref "IC29") (pin "R18") (pinfunction "VCC_R18") (pintype "power_in"))
      (node (ref "IC29") (pin "T13") (pinfunction "VCC_T13") (pintype "power_in"))
      (node (ref "IC29") (pin "T15") (pinfunction "VCC_T15") (pintype "power_in"))
      (node (ref "IC29") (pin "T17") (pinfunction "VCC_T17") (pintype "power_in"))
      (node (ref "IC29") (pin "T19") (pinfunction "VCC_T19") (pintype "power_in"))
      (node (ref "IC29") (pin "U14") (pinfunction "VCC_U14") (pintype "power_in"))
      (node (ref "IC29") (pin "U16") (pinfunction "VCC_U16") (pintype "power_in"))
      (node (ref "IC29") (pin "U18") (pinfunction "VCC_U18") (pintype "power_in"))
      (node (ref "IC29") (pin "U20") (pinfunction "VCC_U20") (pintype "power_in"))
      (node (ref "IC29") (pin "V13") (pinfunction "VCC_V13") (pintype "power_in"))
      (node (ref "IC29") (pin "V15") (pinfunction "VCC_V15") (pintype "power_in"))
      (node (ref "IC29") (pin "V17") (pinfunction "VCC_V17") (pintype "power_in"))
      (node (ref "IC29") (pin "V19") (pinfunction "VCC_V19") (pintype "power_in"))
      (node (ref "IC29") (pin "W14") (pinfunction "VCC_W14") (pintype "power_in"))
      (node (ref "IC29") (pin "W16") (pinfunction "VCC_W16") (pintype "power_in"))
      (node (ref "IC29") (pin "W18") (pinfunction "VCC_W18") (pintype "power_in"))
      (node (ref "IC29") (pin "W20") (pinfunction "VCC_W20") (pintype "power_in"))
    )
    (net (code "4") (name "VCC1P1E_FPGA") (class "Default")
      (node (ref "C348") (pin "2") (pinfunction "2_2") (pintype "passive"))
      (node (ref "C349") (pin "2") (pinfunction "2_2") (pintype "passive"))
      (node (ref "C350") (pin "2") (pinfunction "2_2") (pintype "passive"))
      (node (ref "C351") (pin "2") (pinfunction "2_2") (pintype "passive"))
      (node (ref "C352") (pin "2") (pinfunction "2_2") (pintype "passive"))
      (node (ref "C353") (pin "1") (pinfunction "1_1") (pintype "passive"))
      (node (ref "FR78") (pin "2") (pinfunction "2_2") (pintype "passive"))
      (node (ref "IC29") (pin "AA5") (pinfunction "VCCE_GXBL_AA5") (pintype "power_in"))
      (node (ref "IC29") (pin "AD6") (pinfunction "VCCE_GXBL_AD6") (pintype "power_in"))
      (node (ref "IC29") (pin "J5") (pinfunction "VCCE_GXBL_J5") (pintype "power_in"))
      (node (ref "IC29") (pin "M6") (pinfunction "VCCE_GXBL_M6") (pintype "power_in"))
      (node (ref "IC29") (pin "N5") (pinfunction "VCCE_GXBL_N5") (pintype "power_in"))
      (node (ref "IC29") (pin "T6") (pinfunction "VCCE_GXBL_T6") (pintype "power_in"))
      (node (ref "IC29") (pin "U5") (pinfunction "VCCE_GXBL_U5") (pintype "power_in"))
      (node (ref "IC29") (pin "Y6") (pinfunction "VCCE_GXBL_Y6") (pintype "power_in"))
    )
    (net (code "5") (name "VCC1P1L_FPGA") (class "Default")
      (node (ref "C342") (pin "2") (pinfunction "2_2") (pintype "passive"))
      (node (ref "C343") (pin "2") (pinfunction "2_2") (pintype "passive"))
      (node (ref "C344") (pin "2") (pinfunction "2_2") (pintype "passive"))
      (node (ref "C345") (pin "2") (pinfunction "2_2") (pintype "passive"))
      (node (ref "C346") (pin "2") (pinfunction "2_2") (pintype "passive"))
      (node (ref "C347") (pin "1") (pinfunction "1_1") (pintype "passive"))
      (node (ref "FR77") (pin "2") (pinfunction "2_2") (pintype "passive"))
      (node (ref "IC29") (pin "AC5") (pinfunction "VCCL_GXBL_AC5") (pintype "power_in"))
      (node (ref "IC29") (pin "L5") (pinfunction "VCCL_GXBL_L5") (pintype "power_in"))
      (node (ref "IC29") (pin "R5") (pinfunction "VCCL_GXBL_R5") (pintype "power_in"))
      (node (ref "IC29") (pin "W5") (pinfunction "VCCL_GXBL_W5") (pintype "power_in"))
    )
    (net (code "6") (name "VCC1P5") (class "Default")
      (node (ref "C354") (pin "2") (pinfunction "2_2") (pintype "passive"))
      (node (ref "C355") (pin "2") (pinfunction "2_2") (pintype "passive"))
      (node (ref "C356") (pin "2") (pinfunction "2_2") (pintype "passive"))
      (node (ref "C357") (pin "2") (pinfunction "2_2") (pintype "passive"))
      (node (ref "C358") (pin "2") (pinfunction "2_2") (pintype "passive"))
      (node (ref "C359") (pin "1") (pinfunction "1_1") (pintype "passive"))
      (node (ref "IC29") (pin "A22") (pinfunction "VCCIO7A_A22") (pintype "power_in"))
      (node (ref "IC29") (pin "A7") (pinfunction "VCCIO8A_A7") (pintype "power_in"))
      (node (ref "IC29") (pin "AA12") (pinfunction "VCCIO3B_AA12") (pintype "power_in"))
      (node (ref "IC29") (pin "AB15") (pinfunction "VCCIO4A_AB15") (pintype "power_in"))
      (node (ref "IC29") (pin "AC18") (pinfunction "VCCIO4A_AC18") (pintype "power_in"))
      (node (ref "IC29") (pin "AD21") (pinfunction "VCCIO4A_AD21") (pintype "power_in"))
      (node (ref "IC29") (pin "AE14") (pinfunction "VCCIO3B_AE14") (pintype "power_in"))
      (node (ref "IC29") (pin "AF17") (pinfunction "VCCIO4A_AF17") (pintype "power_in"))
      (node (ref "IC29") (pin "AG10") (pinfunction "VCCIO3B_AG10") (pintype "power_in"))
      (node (ref "IC29") (pin "AG20") (pinfunction "VCCIO4A_AG20") (pintype "power_in"))
      (node (ref "IC29") (pin "AH13") (pinfunction "VCCIO3B_AH13") (pintype "power_in"))
      (node (ref "IC29") (pin "AH23") (pinfunction "VCCIO4A_AH23") (pintype "power_in"))
      (node (ref "IC29") (pin "AJ16") (pinfunction "VCCIO4A_AJ16") (pintype "power_in"))
      (node (ref "IC29") (pin "AJ26") (pinfunction "VCCIO4A_AJ26") (pintype "power_in"))
      (node (ref "IC29") (pin "AK19") (pinfunction "VCCIO4A_AK19") (pintype "power_in"))
      (node (ref "IC29") (pin "AK4") (pinfunction "VCCIO3B_AK4") (pintype "power_in"))
      (node (ref "IC29") (pin "AK9") (pinfunction "VCCIO3B_AK9") (pintype "power_in"))
      (node (ref "IC29") (pin "B15") (pinfunction "VCCIO7A_B15") (pintype "power_in"))
      (node (ref "IC29") (pin "B25") (pinfunction "VCCIO7A_B25") (pintype "power_in"))
      (node (ref "IC29") (pin "B5") (pinfunction "VCCIO8A_B5") (pintype "power_in"))
      (node (ref "IC29") (pin "C18") (pinfunction "VCCIO7A_C18") (pintype "power_in"))
      (node (ref "IC29") (pin "C8") (pinfunction "VCCIO8A_C8") (pintype "power_in"))
      (node (ref "IC29") (pin "D11") (pinfunction "VCCIO8A_D11") (pintype "power_in"))
      (node (ref "IC29") (pin "D21") (pinfunction "VCCIO7A_D21") (pintype "power_in"))
      (node (ref "IC29") (pin "E14") (pinfunction "VCCIO8A_E14") (pintype "power_in"))
      (node (ref "IC29") (pin "E24") (pinfunction "VCCIO7A_E24") (pintype "power_in"))
      (node (ref "IC29") (pin "F17") (pinfunction "VCCIO7A_F17") (pintype "power_in"))
      (node (ref "IC29") (pin "F7") (pinfunction "VCCIO8A_F7") (pintype "power_in"))
      (node (ref "IC29") (pin "G10") (pinfunction "VCCIO8A_G10") (pintype "power_in"))
      (node (ref "IC29") (pin "G20") (pinfunction "VCCIO7A_G20") (pintype "power_in"))
      (node (ref "IC29") (pin "H13") (pinfunction "VCCIO8A_H13") (pintype "power_in"))
      (node (ref "IC29") (pin "H23") (pinfunction "VCCIO7A_H23") (pintype "power_in"))
      (node (ref "IC29") (pin "J16") (pinfunction "VCCIO8A_J16") (pintype "power_in"))
      (node (ref "IC29") (pin "K19") (pinfunction "VCCIO7A_K19") (pintype "power_in"))
      (node (ref "IC29") (pin "L12") (pinfunction "VCCIO8A_L12") (pintype "power_in"))
      (node (ref "IC29") (pin "Y19") (pinfunction "VCCIO4A_Y19") (pintype "power_in"))
    )
    (net (code "7") (name "VCC1P8") (class "Default")
      (node (ref "C360") (pin "2") (pinfunction "2_2") (pintype "passive"))
      (node (ref "C361") (pin "2") (pinfunction "2_2") (pintype "passive"))
      (node (ref "C362") (pin "2") (pinfunction "2_2") (pintype "passive"))
      (node (ref "C363") (pin "2") (pinfunction "2_2") (pintype "passive"))
      (node (ref "C364") (pin "2") (pinfunction "2_2") (pintype "passive"))
      (node (ref "C365") (pin "1") (pinfunction "1_1") (pintype "passive"))
      (node (ref "IC29") (pin "AC8") (pinfunction "VCCIO3A_AC8") (pintype "power_in"))
      (node (ref "IC29") (pin "AD11") (pinfunction "VCCIO3A_AD11") (pintype "power_in"))
      (node (ref "IC29") (pin "U10") (pinfunction "VCCIO3A_U10") (pintype "power_in"))
      (node (ref "IC29") (pin "Y9") (pinfunction "VCCIO3A_Y9") (pintype "power_in"))
    )
    (net (code "8") (name "VCC2P5") (class "Default")
      (node (ref "C366") (pin "2") (pinfunction "2_2") (pintype "passive"))
      (node (ref "C367") (pin "2") (pinfunction "2_2") (pintype "passive"))
      (node (ref "C368") (pin "2") (pinfunction "2_2") (pintype "passive"))
      (node (ref "C369") (pin "2") (pinfunction "2_2") (pintype "passive"))
      (node (ref "C370") (pin "2") (pinfunction "2_2") (pintype "passive"))
      (node (ref "C371") (pin "1") (pinfunction "1_1") (pintype "passive"))
      (node (ref "FR79") (pin "1") (pinfunction "1_1") (pintype "passive"))
      (node (ref "IC29") (pin "AB11") (pinfunction "VCCPD3A_AB11") (pintype "power_in"))
      (node (ref "IC29") (pin "AC12") (pinfunction "VCCPD3B4A_AC12") (pintype "power_in"))
      (node (ref "IC29") (pin "AC17") (pinfunction "VCCPD3B4A_AC17") (pintype "power_in"))
      (node (ref "IC29") (pin "AC20") (pinfunction "VCCPD3B4A_AC20") (pintype "power_in"))
      (node (ref "IC29") (pin "AD10") (pinfunction "VCCPD3A_AD10") (pintype "power_in"))
      (node (ref "IC29") (pin "AD15") (pinfunction "VCCPD3B4A_AD15") (pintype "power_in"))
      (node (ref "IC29") (pin "AE11") (pinfunction "VCCPD3B4A_AE11") (pintype "power_in"))
      (node (ref "IC29") (pin "AE21") (pinfunction "VCCPD3B4A_AE21") (pintype "power_in"))
      (node (ref "IC29") (pin "D24") (pinfunction "VCCPD7A8A_D24") (pintype "power_in"))
      (node (ref "IC29") (pin "F11") (pinfunction "VCCPD7A8A_F11") (pintype "power_in"))
      (node (ref "IC29") (pin "F21") (pinfunction "VCCPD7A8A_F21") (pintype "power_in"))
      (node (ref "IC29") (pin "F23") (pinfunction "VCCPD7A8A_F23") (pintype "power_in"))
      (node (ref "IC29") (pin "G13") (pinfunction "VCCPD7A8A_G13") (pintype "power_in"))
      (node (ref "IC29") (pin "G16") (pinfunction "VCCPD7A8A_G16") (pintype "power_in"))
      (node (ref "IC29") (pin "G19") (pinfunction "VCCPD7A8A_G19") (pintype "power_in"))
    )
    (net (code "9") (name "VCC2P5H_FPGA") (class "Default")
      (node (ref "C372") (pin "2") (pinfunction "2_2") (pintype "passive"))
      (node (ref "C373") (pin "2") (pinfunction "2_2") (pintype "passive"))
      (node (ref "C374") (pin "2") (pinfunction "2_2") (pintype "passive"))
      (node (ref "C375") (pin "2") (pinfunction "2_2") (pintype "passive"))
      (node (ref "C376") (pin "2") (pinfunction "2_2") (pintype "passive"))
      (node (ref "C377") (pin "1") (pinfunction "1_1") (pintype "passive"))
      (node (ref "FR79") (pin "2") (pinfunction "2_2") (pintype "passive"))
      (node (ref "IC29") (pin "AB23") (pinfunction "VCCA_FPLL_AB23") (pintype "power_in"))
      (node (ref "IC29") (pin "AB6") (pinfunction "VCCH_GXBL_AB6") (pintype "power_in"))
      (node (ref "IC29") (pin "AC10") (pinfunction "VCC_AUX_AC10") (pintype "power_in"))
      (node (ref "IC29") (pin "AC16") (pinfunction "VCC_AUX_AC16") (pintype "power_in"))
      (node (ref "IC29") (pin "AD22") (pinfunction "VCC_AUX_AD22") (pintype "power_in"))
      (node (ref "IC29") (pin "G11") (pinfunction "VCC_AUX_G11") (pintype "power_in"))
      (node (ref "IC29") (pin "H16") (pinfunction "VCC_AUX_H16") (pintype "power_in"))
      (node (ref "IC29") (pin "H22") (pinfunction "VCC_AUX_H22") (pintype "power_in"))
      (node (ref "IC29") (pin "J24") (pinfunction "VCCA_FPLL_J24") (pintype "power_in"))
      (node (ref "IC29") (pin "J8") (pinfunction "VCCA_FPLL_J8") (pintype "power_in"))
      (node (ref "IC29") (pin "K6") (pinfunction "VCCH_GXBL_K6") (pintype "power_in"))
      (node (ref "IC29") (pin "P6") (pinfunction "VCCH_GXBL_P6") (pintype "power_in"))
      (node (ref "IC29") (pin "V6") (pinfunction "VCCH_GXBL_V6") (pintype "power_in"))
      (node (ref "IC29") (pin "Y8") (pinfunction "VCCA_FPLL_Y8") (pintype "power_in"))
      (node (ref "R190") (pin "1") (pinfunction "1_1") (pintype "passive"))
    )
    (net (code "10") (name "VCC3P0_BATT") (class "Default")
      (node (ref "R191") (pin "1") (pinfunction "1_1") (pintype "passive"))
    )
    (net (code "11") (name "VCC3P3") (class "Default")
      (node (ref "IC29") (pin "AB24") (pinfunction "VCCPGM_AB24") (pintype "power_in"))
      (node (ref "IC29") (pin "AC11") (pinfunction "VCCPGM_AC11") (pintype "power_in"))
      (node (ref "IC29") (pin "F10") (pinfunction "VCCPGM_F10") (pintype "power_in"))
    )
    (net (code "12") (name "VDIO_DAC_FPGA") (class "Default")
      (node (ref "C384") (pin "2") (pinfunction "2_2") (pintype "passive"))
      (node (ref "C385") (pin "2") (pinfunction "2_2") (pintype "passive"))
      (node (ref "C386") (pin "2") (pinfunction "2_2") (pintype "passive"))
      (node (ref "C387") (pin "2") (pinfunction "2_2") (pintype "passive"))
      (node (ref "C388") (pin "2") (pinfunction "2_2") (pintype "passive"))
      (node (ref "C389") (pin "1") (pinfunction "1_1") (pintype "passive"))
      (node (ref "IC29") (pin "C28") (pinfunction "VCCIO6A_C28") (pintype "power_in"))
      (node (ref "IC29") (pin "F27") (pinfunction "VCCIO6A_F27") (pintype "power_in"))
      (node (ref "IC29") (pin "G30") (pinfunction "VCCIO6A_G30") (pintype "power_in"))
      (node (ref "IC29") (pin "J26") (pinfunction "VCCIO6A_J26") (pintype "power_in"))
      (node (ref "IC29") (pin "K23") (pinfunction "VCCPD6A_K23") (pintype "power_in"))
      (node (ref "IC29") (pin "K29") (pinfunction "VCCIO6A_K29") (pintype "power_in"))
      (node (ref "IC29") (pin "L22") (pinfunction "VCCIO6A_L22") (pintype "power_in"))
      (node (ref "IC29") (pin "M24") (pinfunction "VCCPD6A_M24") (pintype "power_in"))
      (node (ref "IC29") (pin "M25") (pinfunction "VCCIO6A_M25") (pintype "power_in"))
      (node (ref "IC29") (pin "N28") (pinfunction "VCCIO6A_N28") (pintype "power_in"))
      (node (ref "IC29") (pin "P21") (pinfunction "VCCIO6A_P21") (pintype "power_in"))
      (node (ref "IC29") (pin "P24") (pinfunction "VCCPD6A_P24") (pintype "power_in"))
      (node (ref "IC29") (pin "R24") (pinfunction "VCCIO6A_R24") (pintype "power_in"))
    )
    (net (code "13") (name "VDIO_LMS_FPGA") (class "Default")
      (node (ref "C378") (pin "2") (pinfunction "2_2") (pintype "passive"))
      (node (ref "C379") (pin "2") (pinfunction "2_2") (pintype "passive"))
      (node (ref "C380") (pin "2") (pinfunction "2_2") (pintype "passive"))
      (node (ref "C381") (pin "2") (pinfunction "2_2") (pintype "passive"))
      (node (ref "C382") (pin "2") (pinfunction "2_2") (pintype "passive"))
      (node (ref "C383") (pin "1") (pinfunction "1_1") (pintype "passive"))
      (node (ref "IC29") (pin "AA22") (pinfunction "VCCIO5A_AA22") (pintype "power_in"))
      (node (ref "IC29") (pin "AB25") (pinfunction "VCCIO5A_AB25") (pintype "power_in"))
      (node (ref "IC29") (pin "AC28") (pinfunction "VCCIO5B_AC28") (pintype "power_in"))
      (node (ref "IC29") (pin "AE24") (pinfunction "VCCIO5A_AE24") (pintype "power_in"))
      (node (ref "IC29") (pin "AF27") (pinfunction "VCCIO5A_AF27") (pintype "power_in"))
      (node (ref "IC29") (pin "AG30") (pinfunction "VCCIO5B_AG30") (pintype "power_in"))
      (node (ref "IC29") (pin "T26") (pinfunction "VCCPD5B_T26") (pintype "power_in"))
      (node (ref "IC29") (pin "T27") (pinfunction "VCCIO5B_T27") (pintype "power_in"))
      (node (ref "IC29") (pin "U24") (pinfunction "VCCPD5B_U24") (pintype "power_in"))
      (node (ref "IC29") (pin "U30") (pinfunction "VCCIO5B_U30") (pintype "power_in"))
      (node (ref "IC29") (pin "W23") (pinfunction "VCCPD5A_W23") (pintype "power_in"))
      (node (ref "IC29") (pin "W25") (pinfunction "VCCPD5A_W25") (pintype "power_in"))
      (node (ref "IC29") (pin "W26") (pinfunction "VCCIO5B_W26") (pintype "power_in"))
      (node (ref "IC29") (pin "Y29") (pinfunction "VCCIO5B_Y29") (pintype "power_in"))
    )
    (net (code "14") (name "VREF_DDR3_BOT") (class "Default")
      (node (ref "IC29") (pin "AH16") (pinfunction "VREFB4AN0_AH16") (pintype "power_in"))
      (node (ref "IC29") (pin "AJ13") (pinfunction "VREFB3BN0_AJ13") (pintype "power_in"))
    )
    (net (code "15") (name "VREF_DDR3_TOP") (class "Default")
      (node (ref "IC29") (pin "B16") (pinfunction "VREFB7AN0_B16") (pintype "power_in"))
      (node (ref "IC29") (pin "B9") (pinfunction "VREFB8AN0_B9") (pintype "power_in"))
    )
  )
)
